# Inverter_Half_H-Bridge_40A_50khz.net
KiCad netlist of a schematic drawn in EAGLE
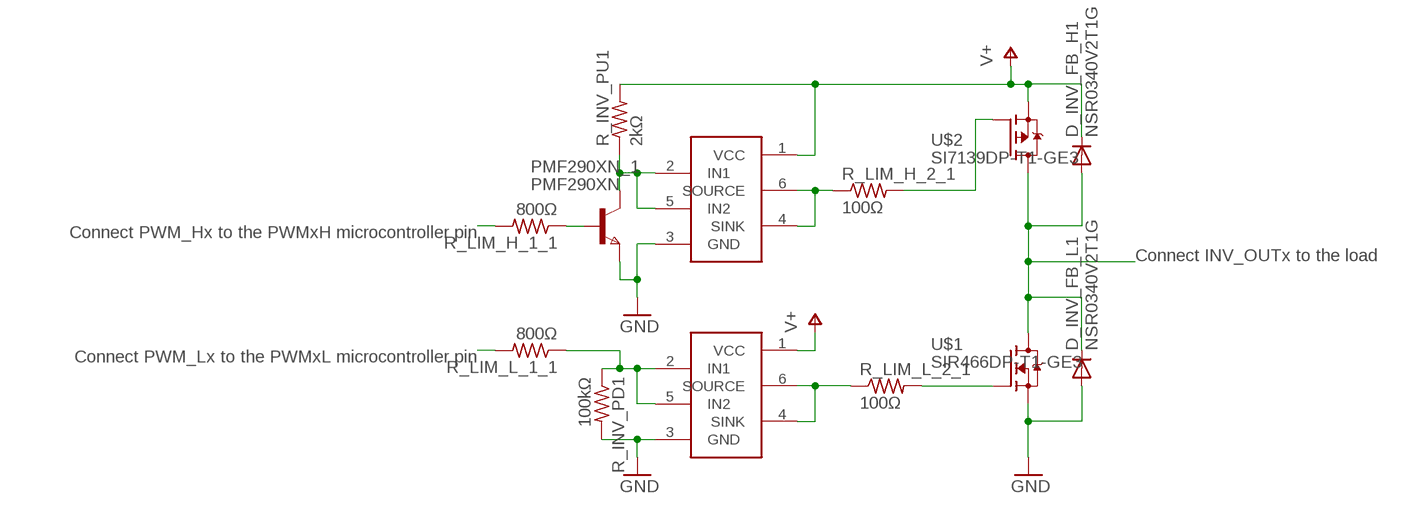
[diagram p0: schematic, sheet 1]

(export (version "E")
  (design (tool "Eeschema 10.0.6"))
  (components
    (comp (ref "D_INV_FB_H1")
      (value "NSR0340V2T1G")
      (footprint "eagle-import:SOD523")
      (libsource (lib "eagle-import") (part "DIODE-SOD523"))
    )
    (comp (ref "D_INV_FB_L1")
      (value "NSR0340V2T1G")
      (footprint "eagle-import:SOD523")
      (libsource (lib "eagle-import") (part "DIODE-SOD523"))
    )
    (comp (ref "PMF290XN_1")
      (value "PMF290XN")
      (footprint "eagle-import:SOT323")
      (libsource (lib "eagle-import") (part "NPNSOT323"))
    )
    (comp (ref "R_INV_PD1")
      (value "100kΩ")
      (footprint "eagle-import:R0603")
      (fields (field (name "PART#") "RNCP0603FTD825RCT-ND"))
      (libsource (lib "eagle-import") (part "R-US_R0603"))
    )
    (comp (ref "R_INV_PU1")
      (value "2kΩ")
      (footprint "eagle-import:R0603")
      (libsource (lib "eagle-import") (part "R-US_R0603"))
    )
    (comp (ref "R_LIM_H_1_1")
      (value "800Ω")
      (footprint "eagle-import:R0603")
      (libsource (lib "eagle-import") (part "R-US_R0603"))
    )
    (comp (ref "R_LIM_H_2_1")
      (value "100Ω")
      (footprint "eagle-import:R0603")
      (libsource (lib "eagle-import") (part "R-US_R0603"))
    )
    (comp (ref "R_LIM_L_1_1")
      (value "800Ω")
      (footprint "eagle-import:R0603")
      (libsource (lib "eagle-import") (part "R-US_R0603"))
    )
    (comp (ref "R_LIM_L_2_1")
      (value "100Ω")
      (footprint "eagle-import:R0603")
      (libsource (lib "eagle-import") (part "R-US_R0603"))
    )
    (comp (ref "U$1")
      (value "SIR466DP-T1-GE3")
      (footprint "eagle-import:S0-8-POWERPAK")
      (libsource (lib "eagle-import") (part "SIR466DP-T1-GE3"))
    )
    (comp (ref "U$2")
      (value "SI7139DP-T1-GE3")
      (footprint "eagle-import:S0-8-POWERPAK")
      (libsource (lib "eagle-import") (part "SI7139DP-T1-GE3"))
    )
    (comp (ref "ZXGD3004E6_H_1")
      (value "ZXGD3004E6")
      (footprint "eagle-import:SOT23-6")
      (libsource (lib "eagle-import") (part "ZXGD3004E6"))
    )
    (comp (ref "ZXGD3004E6_L_1")
      (value "ZXGD3004E6")
      (footprint "eagle-import:SOT23-6")
      (libsource (lib "eagle-import") (part "ZXGD3004E6"))
    )
  )
  (nets
    (net (code "1") (name "GND") (class "Default")
      (node (ref "D_INV_FB_L1") (pin "A") (pinfunction "A_A") (pintype "passive"))
      (node (ref "PMF290XN_1") (pin "3") (pinfunction "E_3") (pintype "passive"))
      (node (ref "R_INV_PD1") (pin "2") (pinfunction "2_2") (pintype "passive"))
      (node (ref "U$1") (pin "1") (pinfunction "S_1") (pintype "passive"))
      (node (ref "U$1") (pin "2") (pinfunction "S_2") (pintype "passive"))
      (node (ref "U$1") (pin "3") (pinfunction "S_3") (pintype "passive"))
      (node (ref "ZXGD3004E6_H_1") (pin "3") (pinfunction "GND_3") (pintype "power_in"))
      (node (ref "ZXGD3004E6_L_1") (pin "3") (pinfunction "GND_3") (pintype "power_in"))
    )
    (net (code "2") (name "Net-(D_INV_FB_H1-PadA)") (class "Default")
      (node (ref "D_INV_FB_H1") (pin "A") (pinfunction "A_A") (pintype "passive"))
      (node (ref "D_INV_FB_L1") (pin "C") (pinfunction "C_C") (pintype "passive"))
      (node (ref "U$1") (pin "5") (pinfunction "D_5") (pintype "passive"))
      (node (ref "U$1") (pin "6") (pinfunction "D_6") (pintype "passive"))
      (node (ref "U$1") (pin "7") (pinfunction "D_7") (pintype "passive"))
      (node (ref "U$1") (pin "8") (pinfunction "D_8") (pintype "passive"))
      (node (ref "U$1") (pin "P$1") (pinfunction "D_P$1") (pintype "passive"))
      (node (ref "U$2") (pin "5") (pinfunction "D_5") (pintype "passive"))
      (node (ref "U$2") (pin "6") (pinfunction "D_6") (pintype "passive"))
      (node (ref "U$2") (pin "7") (pinfunction "D_7") (pintype "passive"))
      (node (ref "U$2") (pin "8") (pinfunction "D_8") (pintype "passive"))
      (node (ref "U$2") (pin "P$1") (pinfunction "D_P$1") (pintype "passive"))
    )
    (net (code "3") (name "Net-(PMF290XN_1-B)") (class "Default")
      (node (ref "PMF290XN_1") (pin "2") (pinfunction "B_2") (pintype "passive"))
      (node (ref "R_LIM_H_1_1") (pin "1") (pinfunction "1_1") (pintype "passive"))
    )
    (net (code "4") (name "Net-(PMF290XN_1-C)") (class "Default")
      (node (ref "PMF290XN_1") (pin "1") (pinfunction "C_1") (pintype "passive"))
      (node (ref "R_INV_PU1") (pin "1") (pinfunction "1_1") (pintype "passive"))
      (node (ref "ZXGD3004E6_H_1") (pin "2") (pinfunction "IN1_2") (pintype "input"))
      (node (ref "ZXGD3004E6_H_1") (pin "5") (pinfunction "IN2_5") (pintype "input"))
    )
    (net (code "5") (name "Net-(U$1-G)") (class "Default")
      (node (ref "R_LIM_L_2_1") (pin "2") (pinfunction "2_2") (pintype "passive"))
      (node (ref "U$1") (pin "4") (pinfunction "G_4") (pintype "passive"))
    )
    (net (code "6") (name "Net-(U$2-G)") (class "Default")
      (node (ref "R_LIM_H_2_1") (pin "2") (pinfunction "2_2") (pintype "passive"))
      (node (ref "U$2") (pin "4") (pinfunction "G_4") (pintype "passive"))
    )
    (net (code "7") (name "Net-(ZXGD3004E6_H_1-SINK)") (class "Default")
      (node (ref "R_LIM_H_2_1") (pin "1") (pinfunction "1_1") (pintype "passive"))
      (node (ref "ZXGD3004E6_H_1") (pin "4") (pinfunction "SINK_4") (pintype "output"))
      (node (ref "ZXGD3004E6_H_1") (pin "6") (pinfunction "SOURCE_6") (pintype "output"))
    )
    (net (code "8") (name "Net-(ZXGD3004E6_L_1-IN1)") (class "Default")
      (node (ref "R_INV_PD1") (pin "1") (pinfunction "1_1") (pintype "passive"))
      (node (ref "R_LIM_L_1_1") (pin "1") (pinfunction "1_1") (pintype "passive"))
      (node (ref "ZXGD3004E6_L_1") (pin "2") (pinfunction "IN1_2") (pintype "input"))
      (node (ref "ZXGD3004E6_L_1") (pin "5") (pinfunction "IN2_5") (pintype "input"))
    )
    (net (code "9") (name "Net-(ZXGD3004E6_L_1-SINK)") (class "Default")
      (node (ref "R_LIM_L_2_1") (pin "1") (pinfunction "1_1") (pintype "passive"))
      (node (ref "ZXGD3004E6_L_1") (pin "4") (pinfunction "SINK_4") (pintype "output"))
      (node (ref "ZXGD3004E6_L_1") (pin "6") (pinfunction "SOURCE_6") (pintype "output"))
    )
    (net (code "10") (name "V+") (class "Default")
      (node (ref "D_INV_FB_H1") (pin "C") (pinfunction "C_C") (pintype "passive"))
      (node (ref "R_INV_PU1") (pin "2") (pinfunction "2_2") (pintype "passive"))
      (node (ref "U$2") (pin "1") (pinfunction "S_1") (pintype "passive"))
      (node (ref "U$2") (pin "2") (pinfunction "S_2") (pintype "passive"))
      (node (ref "U$2") (pin "3") (pinfunction "S_3") (pintype "passive"))
      (node (ref "ZXGD3004E6_H_1") (pin "1") (pinfunction "VCC_1") (pintype "power_in"))
      (node (ref "ZXGD3004E6_L_1") (pin "1") (pinfunction "VCC_1") (pintype "power_in"))
    )
    (net (code "11") (name "unconnected-(R_LIM_H_1_1-Pad2)") (class "Default")
      (node (ref "R_LIM_H_1_1") (pin "2") (pinfunction "2_2") (pintype "passive"))
    )
    (net (code "12") (name "unconnected-(R_LIM_L_1_1-Pad2)") (class "Default")
      (node (ref "R_LIM_L_1_1") (pin "2") (pinfunction "2_2") (pintype "passive"))
    )
  )
)
